# Schematic2.net
KiCad netlist of a schematic drawn in EasyEDA Pro
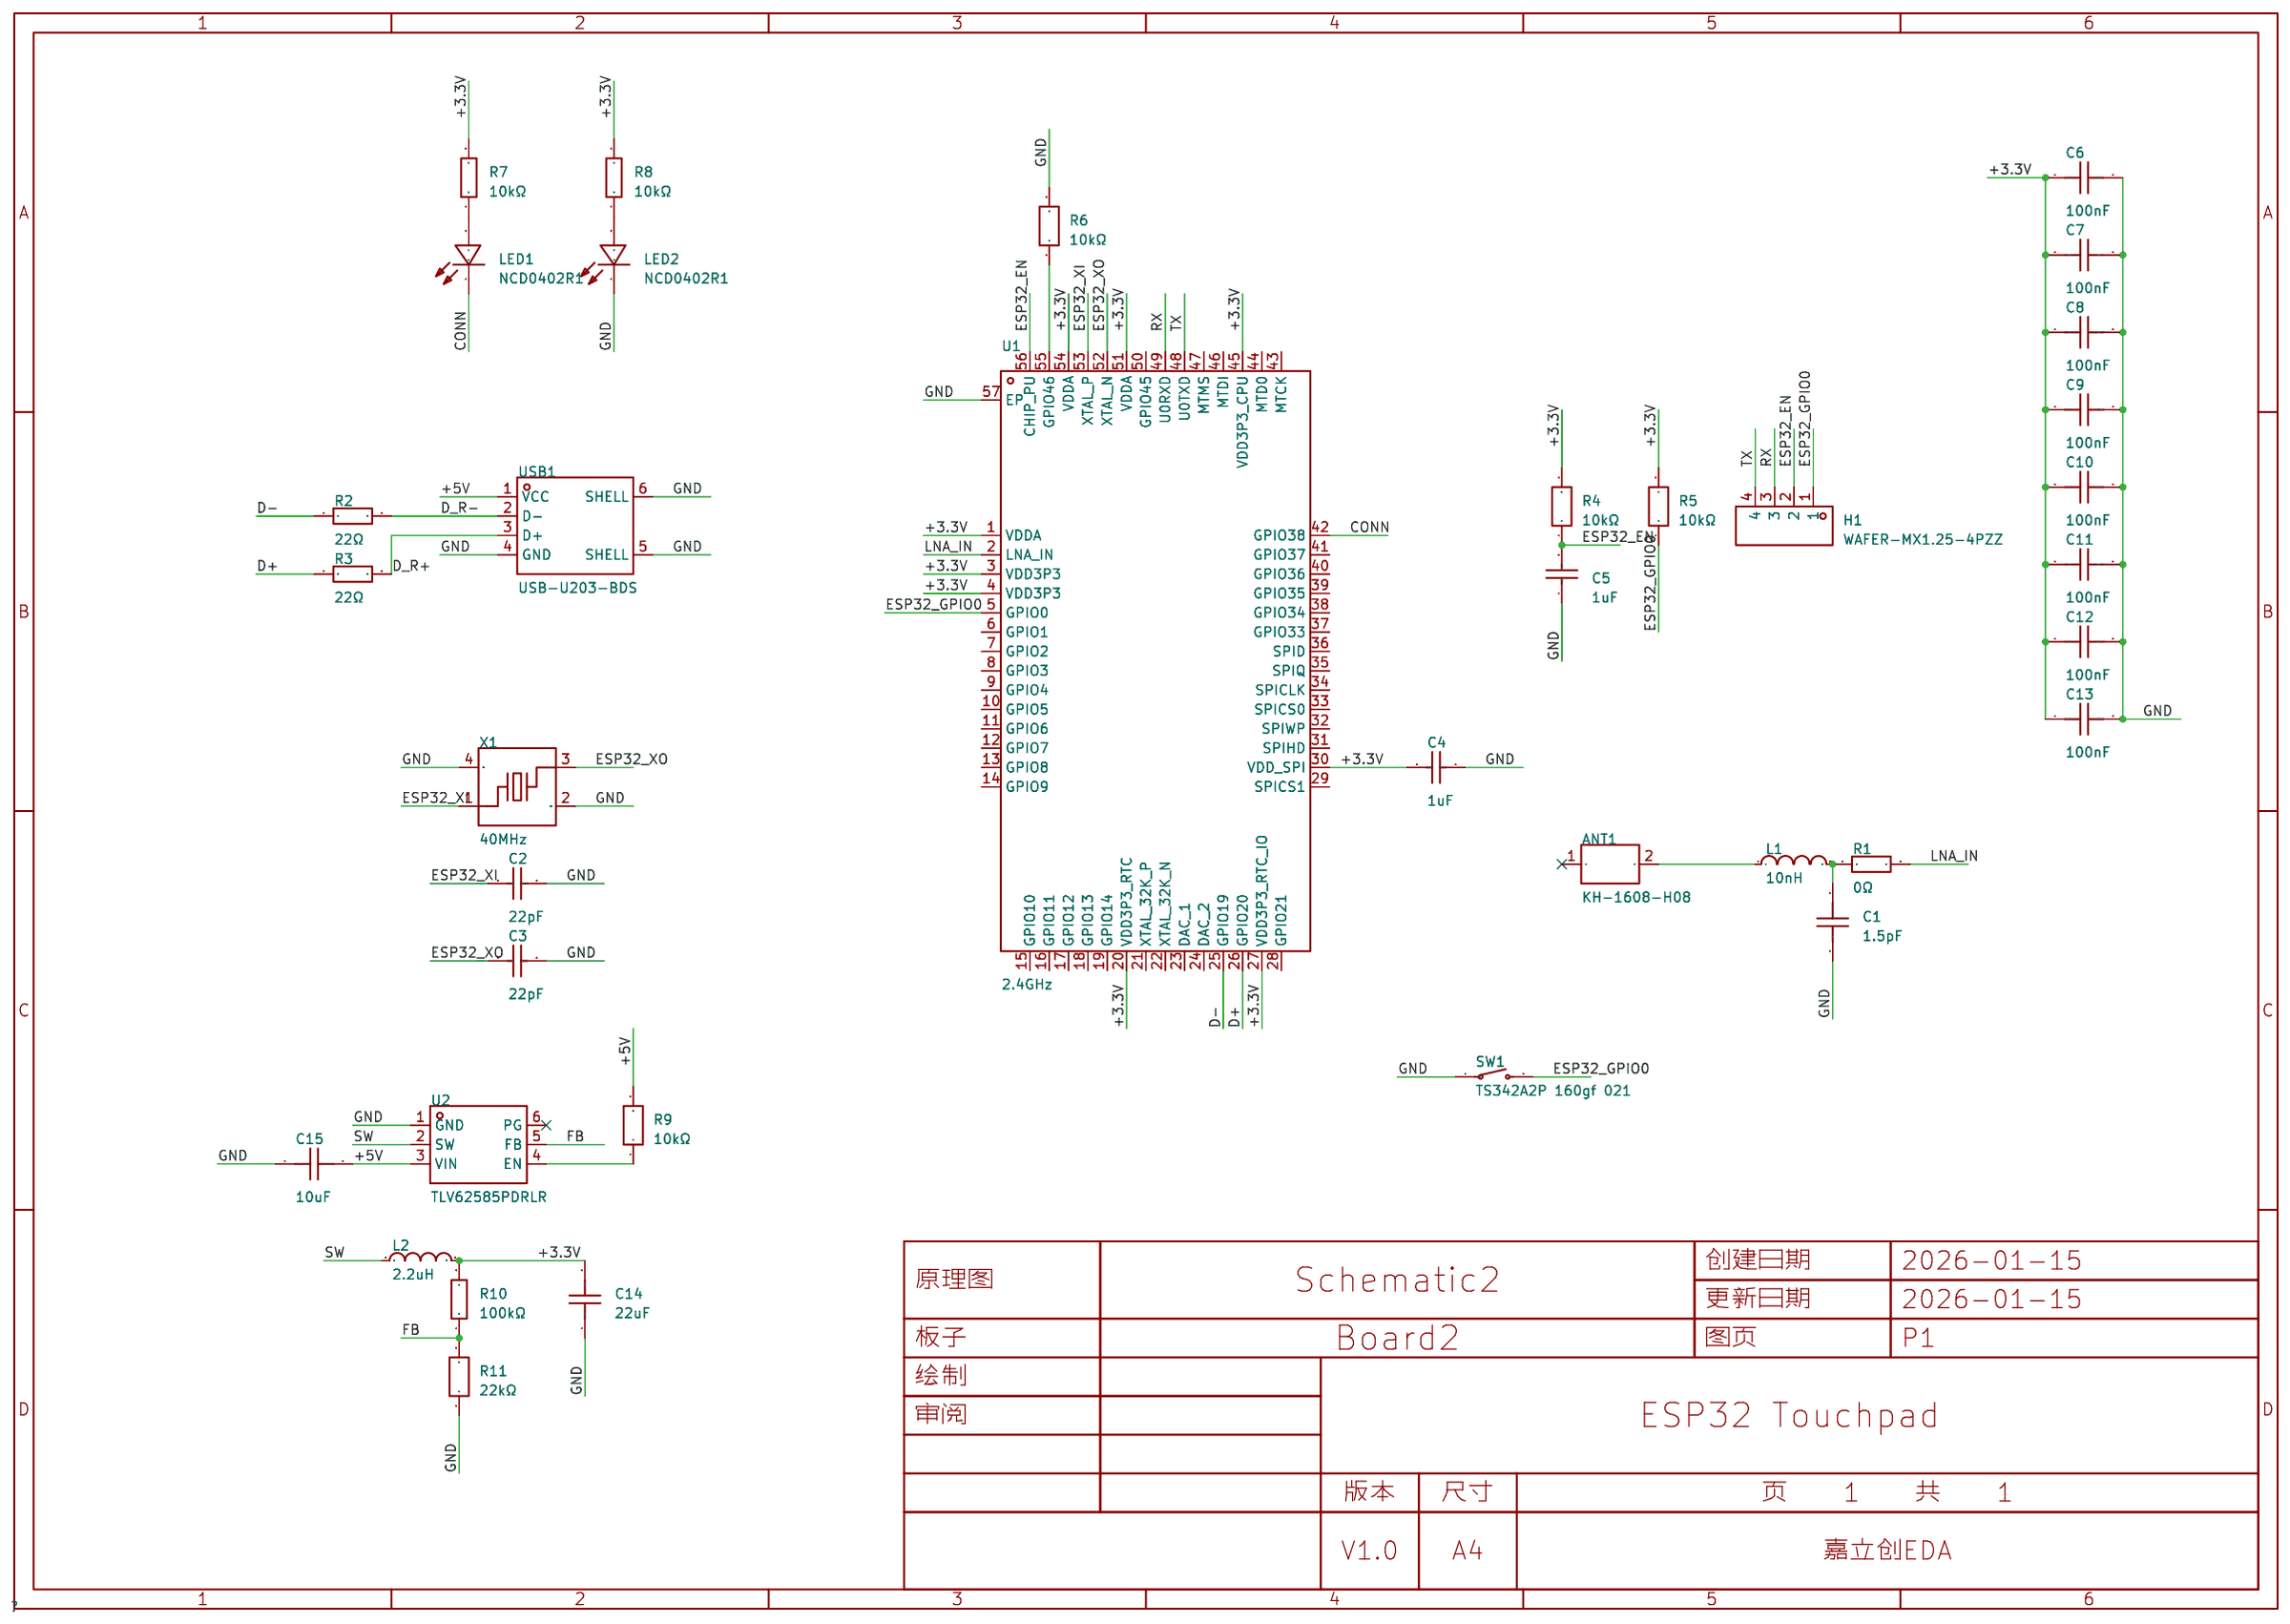
[diagram p0: schematic sheet]

(export (version "E")
  (design (tool "Eeschema 10.0.6"))
  (components
    (comp (ref "ANT1")
      (value "KH-1608-H08")
      (footprint "easyedapro:ANT-SMD_L1.7-W0.9")
      (fields (field (name "Manufacturer") "kinghelm(金航标)"))
      (libsource (lib "easyedapro") (part "KH-1608-H08"))
    )
    (comp (ref "C1")
      (value "1.5pF")
      (footprint "easyedapro:C0402")
      (fields
        (field (name "Manufacturer Part") "GJM1555C1H1R5BB01D")
        (field (name "Manufacturer") "muRata(村田)")
      )
      (libsource (lib "easyedapro") (part "GJM1555C1H1R5BB01D"))
    )
    (comp (ref "C2")
      (value "22pF")
      (footprint "easyedapro:C0201")
      (fields
        (field (name "Manufacturer Part") "GRM0335C1H220JA01D")
        (field (name "Manufacturer") "muRata(村田)")
      )
      (libsource (lib "easyedapro") (part "GRM0335C1H220JA01D"))
    )
    (comp (ref "C3")
      (value "22pF")
      (footprint "easyedapro:C0201")
      (fields
        (field (name "Manufacturer Part") "GRM0335C1H220JA01D")
        (field (name "Manufacturer") "muRata(村田)")
      )
      (libsource (lib "easyedapro") (part "GRM0335C1H220JA01D"))
    )
    (comp (ref "C4")
      (value "1uF")
      (footprint "easyedapro:C0201")
      (fields
        (field (name "Manufacturer Part") "GRM033R61A105ME44D")
        (field (name "Manufacturer") "muRata(村田)")
      )
      (libsource (lib "easyedapro") (part "GRM033R61A105ME44D"))
    )
    (comp (ref "C5")
      (value "1uF")
      (footprint "easyedapro:C0201")
      (fields
        (field (name "Manufacturer Part") "GRM033R61A105ME44D")
        (field (name "Manufacturer") "muRata(村田)")
      )
      (libsource (lib "easyedapro") (part "GRM033R61A105ME44D"))
    )
    (comp (ref "C6")
      (value "100nF")
      (footprint "easyedapro:C0201")
      (fields
        (field (name "Manufacturer Part") "GRM033Z71C104KE14D")
        (field (name "Manufacturer") "muRata(村田)")
      )
      (libsource (lib "easyedapro") (part "GRM033Z71C104KE14D"))
    )
    (comp (ref "C7")
      (value "100nF")
      (footprint "easyedapro:C0201")
      (fields
        (field (name "Manufacturer Part") "GRM033Z71C104KE14D")
        (field (name "Manufacturer") "muRata(村田)")
      )
      (libsource (lib "easyedapro") (part "GRM033Z71C104KE14D"))
    )
    (comp (ref "C8")
      (value "100nF")
      (footprint "easyedapro:C0201")
      (fields
        (field (name "Manufacturer Part") "GRM033Z71C104KE14D")
        (field (name "Manufacturer") "muRata(村田)")
      )
      (libsource (lib "easyedapro") (part "GRM033Z71C104KE14D"))
    )
    (comp (ref "C9")
      (value "100nF")
      (footprint "easyedapro:C0201")
      (fields
        (field (name "Manufacturer Part") "GRM033Z71C104KE14D")
        (field (name "Manufacturer") "muRata(村田)")
      )
      (libsource (lib "easyedapro") (part "GRM033Z71C104KE14D"))
    )
    (comp (ref "C10")
      (value "100nF")
      (footprint "easyedapro:C0201")
      (fields
        (field (name "Manufacturer Part") "GRM033Z71C104KE14D")
        (field (name "Manufacturer") "muRata(村田)")
      )
      (libsource (lib "easyedapro") (part "GRM033Z71C104KE14D"))
    )
    (comp (ref "C11")
      (value "100nF")
      (footprint "easyedapro:C0201")
      (fields
        (field (name "Manufacturer Part") "GRM033Z71C104KE14D")
        (field (name "Manufacturer") "muRata(村田)")
      )
      (libsource (lib "easyedapro") (part "GRM033Z71C104KE14D"))
    )
    (comp (ref "C12")
      (value "100nF")
      (footprint "easyedapro:C0201")
      (fields
        (field (name "Manufacturer Part") "GRM033Z71C104KE14D")
        (field (name "Manufacturer") "muRata(村田)")
      )
      (libsource (lib "easyedapro") (part "GRM033Z71C104KE14D"))
    )
    (comp (ref "C13")
      (value "100nF")
      (footprint "easyedapro:C0201")
      (fields
        (field (name "Manufacturer Part") "GRM033Z71C104KE14D")
        (field (name "Manufacturer") "muRata(村田)")
      )
      (libsource (lib "easyedapro") (part "GRM033Z71C104KE14D"))
    )
    (comp (ref "C14")
      (value "22uF")
      (footprint "easyedapro:C0402")
      (description "容值:22uF;精度:±20%;额定电压:6.3V;温度系数:X5R;")
      (fields
        (field (name "Manufacturer Part") "GRM155R60J226ME11D")
        (field (name "Manufacturer") "muRata(村田)")
      )
      (libsource (lib "easyedapro") (part "GRM155R60J226ME11D"))
    )
    (comp (ref "C15")
      (value "10uF")
      (footprint "easyedapro:C0402")
      (fields
        (field (name "Manufacturer Part") "CL05A106MP5NUNC")
        (field (name "Manufacturer") "SAMSUNG(三星)")
      )
      (libsource (lib "easyedapro") (part "CL05A106MP5NUNC_C315248"))
    )
    (comp (ref "H1")
      (value "WAFER-MX1.25-4PZZ")
      (footprint "easyedapro:CONN-TH_4P-P1.25_WAFER-MX1.25-4PZZ")
      (fields (field (name "Manufacturer") "XUNPU(讯普)"))
      (libsource (lib "easyedapro") (part "WAFER-MX1.25-4PZZ"))
    )
    (comp (ref "L1")
      (value "10nH")
      (footprint "easyedapro:L0402-RD")
      (fields (field (name "Manufacturer Part") "LQG15HS10NJ02D") (field (name "Manufacturer") "muRata(村田)"))
      (libsource (lib "easyedapro") (part "LQG15HS10NJ02D"))
    )
    (comp (ref "L2")
      (value "2.2uH")
      (footprint "easyedapro:IND-SMD_L2.0-W1.2_FTC201210S")
      (fields
        (field (name "Manufacturer Part") "FTC201210S2R2MBCA")
        (field (name "Manufacturer") "cjiang(长江微电)")
      )
      (libsource (lib "easyedapro") (part "FTC201210S2R2MBCA"))
    )
    (comp (ref "LED1")
      (value "NCD0402R1")
      (footprint "easyedapro:LED0402-RD")
      (fields (field (name "Manufacturer") "国星光电"))
      (libsource (lib "easyedapro") (part "FC-F1005HRK-620H5"))
    )
    (comp (ref "LED2")
      (value "NCD0402R1")
      (footprint "easyedapro:LED0402-RD")
      (fields (field (name "Manufacturer") "国星光电"))
      (libsource (lib "easyedapro") (part "FC-F1005HRK-620H5"))
    )
    (comp (ref "R1")
      (value "0Ω")
      (footprint "easyedapro:R0402_1")
      (description "电阻类型:厚膜电阻;阻值:0Ω;精度:±1%;功率:62.5mW;最大工作电压:50V;温度系数:±800ppm/℃;")
      (fields
        (field (name "Manufacturer Part") "0402WGF0000TCE")
        (field (name "Manufacturer") "UNI-ROYAL(厚声)")
      )
      (libsource (lib "easyedapro") (part "0402WGF0000TCE"))
    )
    (comp (ref "R2")
      (value "22Ω")
      (footprint "easyedapro:R0201")
      (description "电阻类型:厚膜电阻;阻值:22Ω;精度:±1%;功率:50mW;工作电压:25V;温度系数:±200ppm/℃;")
      (fields
        (field (name "Manufacturer Part") "0201WMF220JTEE")
        (field (name "Manufacturer") "UNI-ROYAL(厚声)")
      )
      (libsource (lib "easyedapro") (part "0201WMF220JTEE"))
    )
    (comp (ref "R3")
      (value "22Ω")
      (footprint "easyedapro:R0201")
      (description "电阻类型:厚膜电阻;阻值:22Ω;精度:±1%;功率:50mW;工作电压:25V;温度系数:±200ppm/℃;")
      (fields
        (field (name "Manufacturer Part") "0201WMF220JTEE")
        (field (name "Manufacturer") "UNI-ROYAL(厚声)")
      )
      (libsource (lib "easyedapro") (part "0201WMF220JTEE"))
    )
    (comp (ref "R4")
      (value "10kΩ")
      (footprint "easyedapro:R0201")
      (fields
        (field (name "Manufacturer Part") "0201WMF1002TEE")
        (field (name "Manufacturer") "UNI-ROYAL(厚声)")
      )
      (libsource (lib "easyedapro") (part "0201WMF1002TEE"))
    )
    (comp (ref "R5")
      (value "10kΩ")
      (footprint "easyedapro:R0201")
      (fields
        (field (name "Manufacturer Part") "0201WMF1002TEE")
        (field (name "Manufacturer") "UNI-ROYAL(厚声)")
      )
      (libsource (lib "easyedapro") (part "0201WMF1002TEE"))
    )
    (comp (ref "R6")
      (value "10kΩ")
      (footprint "easyedapro:R0201")
      (fields
        (field (name "Manufacturer Part") "0201WMF1002TEE")
        (field (name "Manufacturer") "UNI-ROYAL(厚声)")
      )
      (libsource (lib "easyedapro") (part "0201WMF1002TEE"))
    )
    (comp (ref "R7")
      (value "10kΩ")
      (footprint "easyedapro:R0402")
      (description "电阻类型:厚膜电阻;阻值:10kΩ;精度:±1%;功率:62.5mW;工作电压:50V;温度系数:±100ppm/℃;")
      (fields
        (field (name "Manufacturer Part") "0402WGF1002TCE")
        (field (name "Manufacturer") "UNI-ROYAL(厚声)")
      )
      (libsource (lib "easyedapro") (part "0402WGF1002TCE"))
    )
    (comp (ref "R8")
      (value "10kΩ")
      (footprint "easyedapro:R0402")
      (description "电阻类型:厚膜电阻;阻值:10kΩ;精度:±1%;功率:62.5mW;工作电压:50V;温度系数:±100ppm/℃;")
      (fields
        (field (name "Manufacturer Part") "0402WGF1002TCE")
        (field (name "Manufacturer") "UNI-ROYAL(厚声)")
      )
      (libsource (lib "easyedapro") (part "0402WGF1002TCE"))
    )
    (comp (ref "R9")
      (value "10kΩ")
      (footprint "easyedapro:R0201")
      (fields
        (field (name "Manufacturer Part") "0201WMF1002TEE")
        (field (name "Manufacturer") "UNI-ROYAL(厚声)")
      )
      (libsource (lib "easyedapro") (part "0201WMF1002TEE"))
    )
    (comp (ref "R10")
      (value "100kΩ")
      (footprint "easyedapro:R0201")
      (fields
        (field (name "Manufacturer Part") "0201WMF1003TEE")
        (field (name "Manufacturer") "UNI-ROYAL(厚声)")
      )
      (libsource (lib "easyedapro") (part "0201WMF1003TEE"))
    )
    (comp (ref "R11")
      (value "22kΩ")
      (footprint "easyedapro:R0201")
      (fields (field (name "Manufacturer Part") "RC0201FR-0722KL") (field (name "Manufacturer") "YAGEO(国巨)"))
      (libsource (lib "easyedapro") (part "RC0201FR-0722KL"))
    )
    (comp (ref "SW1")
      (value "TS342A2P 160gf 021")
      (footprint "easyedapro:KEY-SMD_L3.9-W3.0-LS5.0")
      (fields (field (name "Manufacturer") "SHOU HAN(首韩)"))
      (libsource (lib "easyedapro") (part "TS342A2P 160GF 021"))
    )
    (comp (ref "U1")
      (value "2.4GHz")
      (footprint "easyedapro:QFN-56_L7.0-W7.0-P0.40-TL-EP4.6")
      (description "核心芯片:ESP32-S2芯片;频率:2.4GHz;发射功率:19.5dBm;")
      (fields
        (field (name "Manufacturer Part") "ESP32-S2FN4R2")
        (field (name "Manufacturer") "ESPRESSIF(乐鑫)")
      )
      (libsource (lib "easyedapro") (part "ESP32-S2FN4R2"))
    )
    (comp (ref "U2")
      (value "TLV62585PDRLR")
      (footprint "easyedapro:SOT-563_L1.6-W1.2-P0.50-LS1.6-BL")
      (fields (field (name "Manufacturer") "TI(德州仪器)"))
      (libsource (lib "easyedapro") (part "TLV62585PDRLR"))
    )
    (comp (ref "USB1")
      (value "USB-U203-BDS")
      (footprint "easyedapro:USB-SMD_USB-U203-BDS")
      (fields (field (name "Manufacturer") "HANBO(汉博)"))
      (libsource (lib "easyedapro") (part "USB-U203-BDS"))
    )
    (comp (ref "X1")
      (value "40MHz")
      (footprint "easyedapro:CRYSTAL-SMD_4P-L1.6-W1.2-BL")
      (fields
        (field (name "Manufacturer Part") "SX0B40.000F0810F30")
        (field (name "Manufacturer") "SCTF(星通时频)")
      )
      (libsource (lib "easyedapro") (part "SX0B40.000F0810F30"))
    )
  )
  (nets
    (net (code "1") (name "/+3.3V") (class "Default")
      (node (ref "C10") (pin "1") (pinfunction "1_1") (pintype "unspecified"))
      (node (ref "C11") (pin "1") (pinfunction "1_1") (pintype "unspecified"))
      (node (ref "C12") (pin "1") (pinfunction "1_1") (pintype "unspecified"))
      (node (ref "C13") (pin "1") (pinfunction "1_1") (pintype "unspecified"))
      (node (ref "C14") (pin "2") (pinfunction "2_2") (pintype "unspecified"))
      (node (ref "C4") (pin "1") (pinfunction "1_1") (pintype "input"))
      (node (ref "C6") (pin "1") (pinfunction "1_1") (pintype "unspecified"))
      (node (ref "C7") (pin "1") (pinfunction "1_1") (pintype "unspecified"))
      (node (ref "C8") (pin "1") (pinfunction "1_1") (pintype "unspecified"))
      (node (ref "C9") (pin "1") (pinfunction "1_1") (pintype "unspecified"))
      (node (ref "L2") (pin "2") (pinfunction "2_2") (pintype "unspecified"))
      (node (ref "R10") (pin "2") (pinfunction "2_2") (pintype "unspecified"))
      (node (ref "R4") (pin "2") (pinfunction "2_2") (pintype "unspecified"))
      (node (ref "R5") (pin "2") (pinfunction "2_2") (pintype "unspecified"))
      (node (ref "R7") (pin "2") (pinfunction "2_2") (pintype "input"))
      (node (ref "R8") (pin "2") (pinfunction "2_2") (pintype "input"))
      (node (ref "U1") (pin "1") (pinfunction "VDDA_1") (pintype "unspecified"))
      (node (ref "U1") (pin "20") (pinfunction "VDD3P3_RTC_20") (pintype "unspecified"))
      (node (ref "U1") (pin "27") (pinfunction "VDD3P3_RTC_IO_27") (pintype "unspecified"))
      (node (ref "U1") (pin "3") (pinfunction "VDD3P3_3") (pintype "unspecified"))
      (node (ref "U1") (pin "30") (pinfunction "VDD_SPI_30") (pintype "unspecified"))
      (node (ref "U1") (pin "4") (pinfunction "VDD3P3_4") (pintype "unspecified"))
      (node (ref "U1") (pin "45") (pinfunction "VDD3P3_CPU_45") (pintype "unspecified"))
      (node (ref "U1") (pin "51") (pinfunction "VDDA_51") (pintype "unspecified"))
      (node (ref "U1") (pin "54") (pinfunction "VDDA_54") (pintype "unspecified"))
    )
    (net (code "2") (name "/+5V") (class "Default")
      (node (ref "C15") (pin "2") (pinfunction "2_2") (pintype "unspecified"))
      (node (ref "R9") (pin "2") (pinfunction "2_2") (pintype "unspecified"))
      (node (ref "U2") (pin "3") (pinfunction "VIN_3") (pintype "unspecified"))
      (node (ref "USB1") (pin "1") (pinfunction "VCC_1") (pintype "unspecified"))
    )
    (net (code "3") (name "/CONN") (class "Default")
      (node (ref "LED1") (pin "1") (pinfunction "K_1") (pintype "unspecified"))
      (node (ref "U1") (pin "42") (pinfunction "GPIO38_42") (pintype "unspecified"))
    )
    (net (code "4") (name "/D+") (class "Default")
      (node (ref "R3") (pin "1") (pinfunction "1_1") (pintype "unspecified"))
      (node (ref "U1") (pin "26") (pinfunction "GPIO20_26") (pintype "unspecified"))
    )
    (net (code "5") (name "/D-") (class "Default")
      (node (ref "R2") (pin "1") (pinfunction "1_1") (pintype "unspecified"))
      (node (ref "U1") (pin "25") (pinfunction "GPIO19_25") (pintype "unspecified"))
    )
    (net (code "6") (name "/D_R+") (class "Default")
      (node (ref "R3") (pin "2") (pinfunction "2_2") (pintype "unspecified"))
      (node (ref "USB1") (pin "3") (pinfunction "D+_3") (pintype "unspecified"))
    )
    (net (code "7") (name "/D_R-") (class "Default")
      (node (ref "R2") (pin "2") (pinfunction "2_2") (pintype "unspecified"))
      (node (ref "USB1") (pin "2") (pinfunction "D-_2") (pintype "unspecified"))
    )
    (net (code "8") (name "/ESP32_EN") (class "Default")
      (node (ref "C5") (pin "2") (pinfunction "2_2") (pintype "input"))
      (node (ref "H1") (pin "2") (pinfunction "2_2") (pintype "unspecified"))
      (node (ref "R4") (pin "1") (pinfunction "1_1") (pintype "unspecified"))
      (node (ref "U1") (pin "56") (pinfunction "CHIP_PU_56") (pintype "unspecified"))
    )
    (net (code "9") (name "/ESP32_GPIO0") (class "Default")
      (node (ref "H1") (pin "1") (pinfunction "1_1") (pintype "unspecified"))
      (node (ref "R5") (pin "1") (pinfunction "1_1") (pintype "unspecified"))
      (node (ref "SW1") (pin "2") (pinfunction "2_2") (pintype "unspecified"))
      (node (ref "U1") (pin "5") (pinfunction "GPIO0_5") (pintype "unspecified"))
    )
    (net (code "10") (name "/ESP32_XI") (class "Default")
      (node (ref "C2") (pin "1") (pinfunction "1_1") (pintype "input"))
      (node (ref "U1") (pin "53") (pinfunction "XTAL_P_53") (pintype "unspecified"))
      (node (ref "X1") (pin "1") (pinfunction "1_1") (pintype "input"))
    )
    (net (code "11") (name "/ESP32_XO") (class "Default")
      (node (ref "C3") (pin "1") (pinfunction "1_1") (pintype "input"))
      (node (ref "U1") (pin "52") (pinfunction "XTAL_N_52") (pintype "unspecified"))
      (node (ref "X1") (pin "3") (pinfunction "3_3") (pintype "input"))
    )
    (net (code "12") (name "/FB") (class "Default")
      (node (ref "R10") (pin "1") (pinfunction "1_1") (pintype "unspecified"))
      (node (ref "R11") (pin "2") (pinfunction "2_2") (pintype "unspecified"))
      (node (ref "U2") (pin "5") (pinfunction "FB_5") (pintype "unspecified"))
    )
    (net (code "13") (name "/GND") (class "Default")
      (node (ref "C1") (pin "1") (pinfunction "1_1") (pintype "unspecified"))
      (node (ref "C10") (pin "2") (pinfunction "2_2") (pintype "unspecified"))
      (node (ref "C11") (pin "2") (pinfunction "2_2") (pintype "unspecified"))
      (node (ref "C12") (pin "2") (pinfunction "2_2") (pintype "unspecified"))
      (node (ref "C13") (pin "2") (pinfunction "2_2") (pintype "unspecified"))
      (node (ref "C14") (pin "1") (pinfunction "1_1") (pintype "unspecified"))
      (node (ref "C15") (pin "1") (pinfunction "1_1") (pintype "unspecified"))
      (node (ref "C2") (pin "2") (pinfunction "2_2") (pintype "input"))
      (node (ref "C3") (pin "2") (pinfunction "2_2") (pintype "input"))
      (node (ref "C4") (pin "2") (pinfunction "2_2") (pintype "input"))
      (node (ref "C5") (pin "1") (pinfunction "1_1") (pintype "input"))
      (node (ref "C6") (pin "2") (pinfunction "2_2") (pintype "unspecified"))
      (node (ref "C7") (pin "2") (pinfunction "2_2") (pintype "unspecified"))
      (node (ref "C8") (pin "2") (pinfunction "2_2") (pintype "unspecified"))
      (node (ref "C9") (pin "2") (pinfunction "2_2") (pintype "unspecified"))
      (node (ref "LED2") (pin "1") (pinfunction "K_1") (pintype "unspecified"))
      (node (ref "R11") (pin "1") (pinfunction "1_1") (pintype "unspecified"))
      (node (ref "R6") (pin "2") (pinfunction "2_2") (pintype "unspecified"))
      (node (ref "SW1") (pin "1") (pinfunction "1_1") (pintype "unspecified"))
      (node (ref "U1") (pin "57") (pinfunction "EP_57") (pintype "unspecified"))
      (node (ref "U2") (pin "1") (pinfunction "GND_1") (pintype "unspecified"))
      (node (ref "USB1") (pin "4") (pinfunction "GND_4") (pintype "unspecified"))
      (node (ref "USB1") (pin "5") (pinfunction "SHELL_5") (pintype "unspecified"))
      (node (ref "USB1") (pin "6") (pinfunction "SHELL_6") (pintype "unspecified"))
      (node (ref "X1") (pin "2") (pinfunction "GND_2") (pintype "input"))
      (node (ref "X1") (pin "4") (pinfunction "GND_4") (pintype "input"))
    )
    (net (code "14") (name "/LNA_IN") (class "Default")
      (node (ref "R1") (pin "2") (pinfunction "2_2") (pintype "input"))
      (node (ref "U1") (pin "2") (pinfunction "LNA_IN_2") (pintype "unspecified"))
    )
    (net (code "15") (name "/RX") (class "Default")
      (node (ref "H1") (pin "3") (pinfunction "3_3") (pintype "unspecified"))
      (node (ref "U1") (pin "49") (pinfunction "U0RXD_49") (pintype "unspecified"))
    )
    (net (code "16") (name "/SW") (class "Default")
      (node (ref "L2") (pin "1") (pinfunction "1_1") (pintype "unspecified"))
      (node (ref "U2") (pin "2") (pinfunction "SW_2") (pintype "unspecified"))
    )
    (net (code "17") (name "/TX") (class "Default")
      (node (ref "H1") (pin "4") (pinfunction "4_4") (pintype "unspecified"))
      (node (ref "U1") (pin "48") (pinfunction "U0TXD_48") (pintype "unspecified"))
    )
    (net (code "18") (name "Net-(ANT1-Pad2)") (class "Default")
      (node (ref "ANT1") (pin "2") (pinfunction "2_2") (pintype "unspecified"))
      (node (ref "L1") (pin "1") (pinfunction "1_1") (pintype "unspecified"))
    )
    (net (code "19") (name "Net-(C1-Pad2)") (class "Default")
      (node (ref "C1") (pin "2") (pinfunction "2_2") (pintype "unspecified"))
      (node (ref "L1") (pin "2") (pinfunction "2_2") (pintype "unspecified"))
      (node (ref "R1") (pin "1") (pinfunction "1_1") (pintype "input"))
    )
    (net (code "20") (name "Net-(LED1-A)") (class "Default")
      (node (ref "LED1") (pin "2") (pinfunction "A_2") (pintype "unspecified"))
      (node (ref "R7") (pin "1") (pinfunction "1_1") (pintype "input"))
    )
    (net (code "21") (name "Net-(LED2-A)") (class "Default")
      (node (ref "LED2") (pin "2") (pinfunction "A_2") (pintype "unspecified"))
      (node (ref "R8") (pin "1") (pinfunction "1_1") (pintype "input"))
    )
    (net (code "22") (name "Net-(U1-GPIO46)") (class "Default")
      (node (ref "R6") (pin "1") (pinfunction "1_1") (pintype "unspecified"))
      (node (ref "U1") (pin "55") (pinfunction "GPIO46_55") (pintype "unspecified"))
    )
    (net (code "23") (name "Net-(U2-EN)") (class "Default")
      (node (ref "R9") (pin "1") (pinfunction "1_1") (pintype "unspecified"))
      (node (ref "U2") (pin "4") (pinfunction "EN_4") (pintype "unspecified"))
    )
    (net (code "24") (name "unconnected-(ANT1-Pad1)") (class "Default")
      (node (ref "ANT1") (pin "1") (pinfunction "1_1") (pintype "unspecified+no_connect"))
    )
    (net (code "25") (name "unconnected-(U1-DAC_1-Pad23)") (class "Default")
      (node (ref "U1") (pin "23") (pinfunction "DAC_1_23") (pintype "unspecified"))
    )
    (net (code "26") (name "unconnected-(U1-DAC_2-Pad24)") (class "Default")
      (node (ref "U1") (pin "24") (pinfunction "DAC_2_24") (pintype "unspecified"))
    )
    (net (code "27") (name "unconnected-(U1-GPIO1-Pad6)") (class "Default")
      (node (ref "U1") (pin "6") (pinfunction "GPIO1_6") (pintype "unspecified"))
    )
    (net (code "28") (name "unconnected-(U1-GPIO2-Pad7)") (class "Default")
      (node (ref "U1") (pin "7") (pinfunction "GPIO2_7") (pintype "unspecified"))
    )
    (net (code "29") (name "unconnected-(U1-GPIO3-Pad8)") (class "Default")
      (node (ref "U1") (pin "8") (pinfunction "GPIO3_8") (pintype "unspecified"))
    )
    (net (code "30") (name "unconnected-(U1-GPIO4-Pad9)") (class "Default")
      (node (ref "U1") (pin "9") (pinfunction "GPIO4_9") (pintype "unspecified"))
    )
    (net (code "31") (name "unconnected-(U1-GPIO5-Pad10)") (class "Default")
      (node (ref "U1") (pin "10") (pinfunction "GPIO5_10") (pintype "unspecified"))
    )
    (net (code "32") (name "unconnected-(U1-GPIO6-Pad11)") (class "Default")
      (node (ref "U1") (pin "11") (pinfunction "GPIO6_11") (pintype "unspecified"))
    )
    (net (code "33") (name "unconnected-(U1-GPIO7-Pad12)") (class "Default")
      (node (ref "U1") (pin "12") (pinfunction "GPIO7_12") (pintype "unspecified"))
    )
    (net (code "34") (name "unconnected-(U1-GPIO8-Pad13)") (class "Default")
      (node (ref "U1") (pin "13") (pinfunction "GPIO8_13") (pintype "unspecified"))
    )
    (net (code "35") (name "unconnected-(U1-GPIO9-Pad14)") (class "Default")
      (node (ref "U1") (pin "14") (pinfunction "GPIO9_14") (pintype "unspecified"))
    )
    (net (code "36") (name "unconnected-(U1-GPIO10-Pad15)") (class "Default")
      (node (ref "U1") (pin "15") (pinfunction "GPIO10_15") (pintype "unspecified"))
    )
    (net (code "37") (name "unconnected-(U1-GPIO11-Pad16)") (class "Default")
      (node (ref "U1") (pin "16") (pinfunction "GPIO11_16") (pintype "unspecified"))
    )
    (net (code "38") (name "unconnected-(U1-GPIO12-Pad17)") (class "Default")
      (node (ref "U1") (pin "17") (pinfunction "GPIO12_17") (pintype "unspecified"))
    )
    (net (code "39") (name "unconnected-(U1-GPIO13-Pad18)") (class "Default")
      (node (ref "U1") (pin "18") (pinfunction "GPIO13_18") (pintype "unspecified"))
    )
    (net (code "40") (name "unconnected-(U1-GPIO14-Pad19)") (class "Default")
      (node (ref "U1") (pin "19") (pinfunction "GPIO14_19") (pintype "unspecified"))
    )
    (net (code "41") (name "unconnected-(U1-GPIO21-Pad28)") (class "Default")
      (node (ref "U1") (pin "28") (pinfunction "GPIO21_28") (pintype "unspecified"))
    )
    (net (code "42") (name "unconnected-(U1-GPIO33-Pad37)") (class "Default")
      (node (ref "U1") (pin "37") (pinfunction "GPIO33_37") (pintype "unspecified"))
    )
    (net (code "43") (name "unconnected-(U1-GPIO34-Pad38)") (class "Default")
      (node (ref "U1") (pin "38") (pinfunction "GPIO34_38") (pintype "unspecified"))
    )
    (net (code "44") (name "unconnected-(U1-GPIO35-Pad39)") (class "Default")
      (node (ref "U1") (pin "39") (pinfunction "GPIO35_39") (pintype "unspecified"))
    )
    (net (code "45") (name "unconnected-(U1-GPIO36-Pad40)") (class "Default")
      (node (ref "U1") (pin "40") (pinfunction "GPIO36_40") (pintype "unspecified"))
    )
    (net (code "46") (name "unconnected-(U1-GPIO37-Pad41)") (class "Default")
      (node (ref "U1") (pin "41") (pinfunction "GPIO37_41") (pintype "unspecified"))
    )
    (net (code "47") (name "unconnected-(U1-GPIO45-Pad50)") (class "Default")
      (node (ref "U1") (pin "50") (pinfunction "GPIO45_50") (pintype "unspecified"))
    )
    (net (code "48") (name "unconnected-(U1-MTCK-Pad43)") (class "Default")
      (node (ref "U1") (pin "43") (pinfunction "MTCK_43") (pintype "unspecified"))
    )
    (net (code "49") (name "unconnected-(U1-MTD0-Pad44)") (class "Default")
      (node (ref "U1") (pin "44") (pinfunction "MTD0_44") (pintype "unspecified"))
    )
    (net (code "50") (name "unconnected-(U1-MTDI-Pad46)") (class "Default")
      (node (ref "U1") (pin "46") (pinfunction "MTDI_46") (pintype "unspecified"))
    )
    (net (code "51") (name "unconnected-(U1-MTMS-Pad47)") (class "Default")
      (node (ref "U1") (pin "47") (pinfunction "MTMS_47") (pintype "unspecified"))
    )
    (net (code "52") (name "unconnected-(U1-SPICLK-Pad34)") (class "Default")
      (node (ref "U1") (pin "34") (pinfunction "SPICLK_34") (pintype "unspecified"))
    )
    (net (code "53") (name "unconnected-(U1-SPICS0-Pad33)") (class "Default")
      (node (ref "U1") (pin "33") (pinfunction "SPICS0_33") (pintype "unspecified"))
    )
    (net (code "54") (name "unconnected-(U1-SPICS1-Pad29)") (class "Default")
      (node (ref "U1") (pin "29") (pinfunction "SPICS1_29") (pintype "unspecified"))
    )
    (net (code "55") (name "unconnected-(U1-SPID-Pad36)") (class "Default")
      (node (ref "U1") (pin "36") (pinfunction "SPID_36") (pintype "unspecified"))
    )
    (net (code "56") (name "unconnected-(U1-SPIHD-Pad31)") (class "Default")
      (node (ref "U1") (pin "31") (pinfunction "SPIHD_31") (pintype "unspecified"))
    )
    (net (code "57") (name "unconnected-(U1-SPIQ-Pad35)") (class "Default")
      (node (ref "U1") (pin "35") (pinfunction "SPIQ_35") (pintype "unspecified"))
    )
    (net (code "58") (name "unconnected-(U1-SPIWP-Pad32)") (class "Default")
      (node (ref "U1") (pin "32") (pinfunction "SPIWP_32") (pintype "unspecified"))
    )
    (net (code "59") (name "unconnected-(U1-XTAL_32K_N-Pad22)") (class "Default")
      (node (ref "U1") (pin "22") (pinfunction "XTAL_32K_N_22") (pintype "unspecified"))
    )
    (net (code "60") (name "unconnected-(U1-XTAL_32K_P-Pad21)") (class "Default")
      (node (ref "U1") (pin "21") (pinfunction "XTAL_32K_P_21") (pintype "unspecified"))
    )
    (net (code "61") (name "unconnected-(U2-PG-Pad6)") (class "Default")
      (node (ref "U2") (pin "6") (pinfunction "PG_6") (pintype "unspecified+no_connect"))
    )
  )
)
